# fonte1.net
KiCad netlist of a schematic drawn in EAGLE
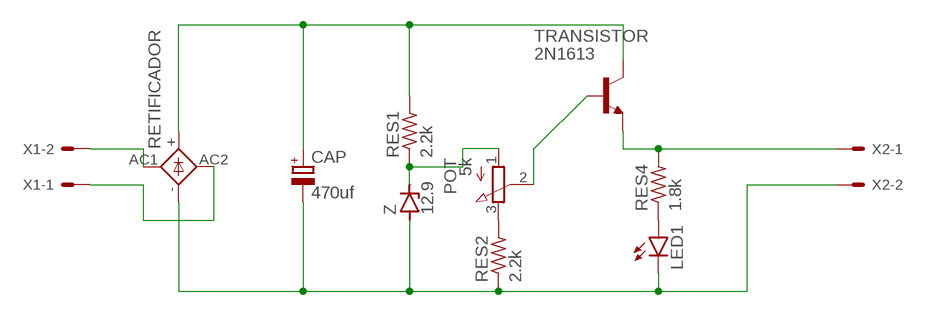
[diagram p0: schematic, sheet 1]

(export (version "E")
  (design (tool "Eeschema 10.0.6"))
  (components
    (comp (ref "CAP")
      (value "470uf")
      (footprint "eagle-import:E3,5-8")
      (libsource (lib "eagle-import") (part "CPOL-EUE3.5-8"))
    )
    (comp (ref "LED1")
      (value "LED3MM")
      (footprint "eagle-import:LED3MM")
      (libsource (lib "eagle-import") (part "LED3MM"))
    )
    (comp (ref "POT")
      (value "5k")
      (footprint "eagle-import:3RP_1610N")
      (libsource (lib "eagle-import") (part "3RP/1610N"))
    )
    (comp (ref "RES1")
      (value "2.2k")
      (footprint "eagle-import:0207_7")
      (libsource (lib "eagle-import") (part "R-US_0207/7"))
    )
    (comp (ref "RES2")
      (value "2.2k")
      (footprint "eagle-import:0207_7")
      (libsource (lib "eagle-import") (part "R-US_0207/7"))
    )
    (comp (ref "RES4")
      (value "1.8k")
      (footprint "eagle-import:0207_7")
      (libsource (lib "eagle-import") (part "R-US_0207/7"))
    )
    (comp (ref "RETIFICADOR")
      (value "1KAB")
      (footprint "eagle-import:1KAB")
      (libsource (lib "eagle-import") (part "1KAB"))
    )
    (comp (ref "TRANSISTOR")
      (value "2N1613")
      (footprint "eagle-import:TO5")
      (libsource (lib "eagle-import") (part "2N1613"))
    )
    (comp (ref "X1")
      (value "KK-156-2")
      (footprint "eagle-import:KK-156-2")
      (fields (field (name "MF") "MOLEX"))
      (libsource (lib "eagle-import") (part "KK-156-2"))
    )
    (comp (ref "X2")
      (value "KK-156-2")
      (footprint "eagle-import:KK-156-2")
      (fields (field (name "MF") "MOLEX"))
      (libsource (lib "eagle-import") (part "KK-156-2"))
    )
    (comp (ref "Z")
      (value "12.9")
      (footprint "eagle-import:C1702-15")
      (libsource (lib "eagle-import") (part "ZENER-DIODEC1702-15"))
    )
  )
  (nets
    (net (code "1") (name "Net-(LED1-C)") (class "Default")
      (node (ref "CAP") (pin "-") (pinfunction "-_-") (pintype "passive"))
      (node (ref "LED1") (pin "K") (pinfunction "C_K") (pintype "passive"))
      (node (ref "RES2") (pin "1") (pinfunction "1_1") (pintype "passive"))
      (node (ref "RETIFICADOR") (pin "-") (pinfunction "-_-") (pintype "passive"))
      (node (ref "X2") (pin "2") (pinfunction "S_2") (pintype "passive"))
      (node (ref "Z") (pin "A") (pinfunction "A_A") (pintype "passive"))
    )
    (net (code "2") (name "Net-(LED1-PadA)") (class "Default")
      (node (ref "LED1") (pin "A") (pinfunction "A_A") (pintype "passive"))
      (node (ref "RES4") (pin "1") (pinfunction "1_1") (pintype "passive"))
    )
    (net (code "3") (name "Net-(POT-A)") (class "Default")
      (node (ref "POT") (pin "1") (pinfunction "A_1") (pintype "passive"))
      (node (ref "RES1") (pin "1") (pinfunction "1_1") (pintype "passive"))
      (node (ref "Z") (pin "C") (pinfunction "C_C") (pintype "passive"))
    )
    (net (code "4") (name "Net-(POT-E)") (class "Default")
      (node (ref "POT") (pin "3") (pinfunction "E_3") (pintype "passive"))
      (node (ref "RES2") (pin "2") (pinfunction "2_2") (pintype "passive"))
    )
    (net (code "5") (name "Net-(POT-S)") (class "Default")
      (node (ref "POT") (pin "2") (pinfunction "S_2") (pintype "passive"))
      (node (ref "TRANSISTOR") (pin "2") (pinfunction "B_2") (pintype "passive"))
    )
    (net (code "6") (name "Net-(TRANSISTOR-C)") (class "Default")
      (node (ref "CAP") (pin "+") (pinfunction "+_+") (pintype "passive"))
      (node (ref "RES1") (pin "2") (pinfunction "2_2") (pintype "passive"))
      (node (ref "RETIFICADOR") (pin "+") (pinfunction "+_+") (pintype "passive"))
      (node (ref "TRANSISTOR") (pin "3") (pinfunction "C_3") (pintype "passive"))
    )
    (net (code "7") (name "Net-(TRANSISTOR-E)") (class "Default")
      (node (ref "RES4") (pin "2") (pinfunction "2_2") (pintype "passive"))
      (node (ref "TRANSISTOR") (pin "1") (pinfunction "E_1") (pintype "passive"))
      (node (ref "X2") (pin "1") (pinfunction "S_1") (pintype "passive"))
    )
    (net (code "8") (name "Net-(X1A-S)") (class "Default")
      (node (ref "RETIFICADOR") (pin "AC2") (pinfunction "AC2_AC2") (pintype "passive"))
      (node (ref "X1") (pin "1") (pinfunction "S_1") (pintype "passive"))
    )
    (net (code "9") (name "Net-(X1B-S)") (class "Default")
      (node (ref "RETIFICADOR") (pin "AC1") (pinfunction "AC1_AC1") (pintype "passive"))
      (node (ref "X1") (pin "2") (pinfunction "S_2") (pintype "passive"))
    )
  )
)
